# oresat1b-minusz-end-cap.net
KiCad netlist of a schematic drawn in EAGLE
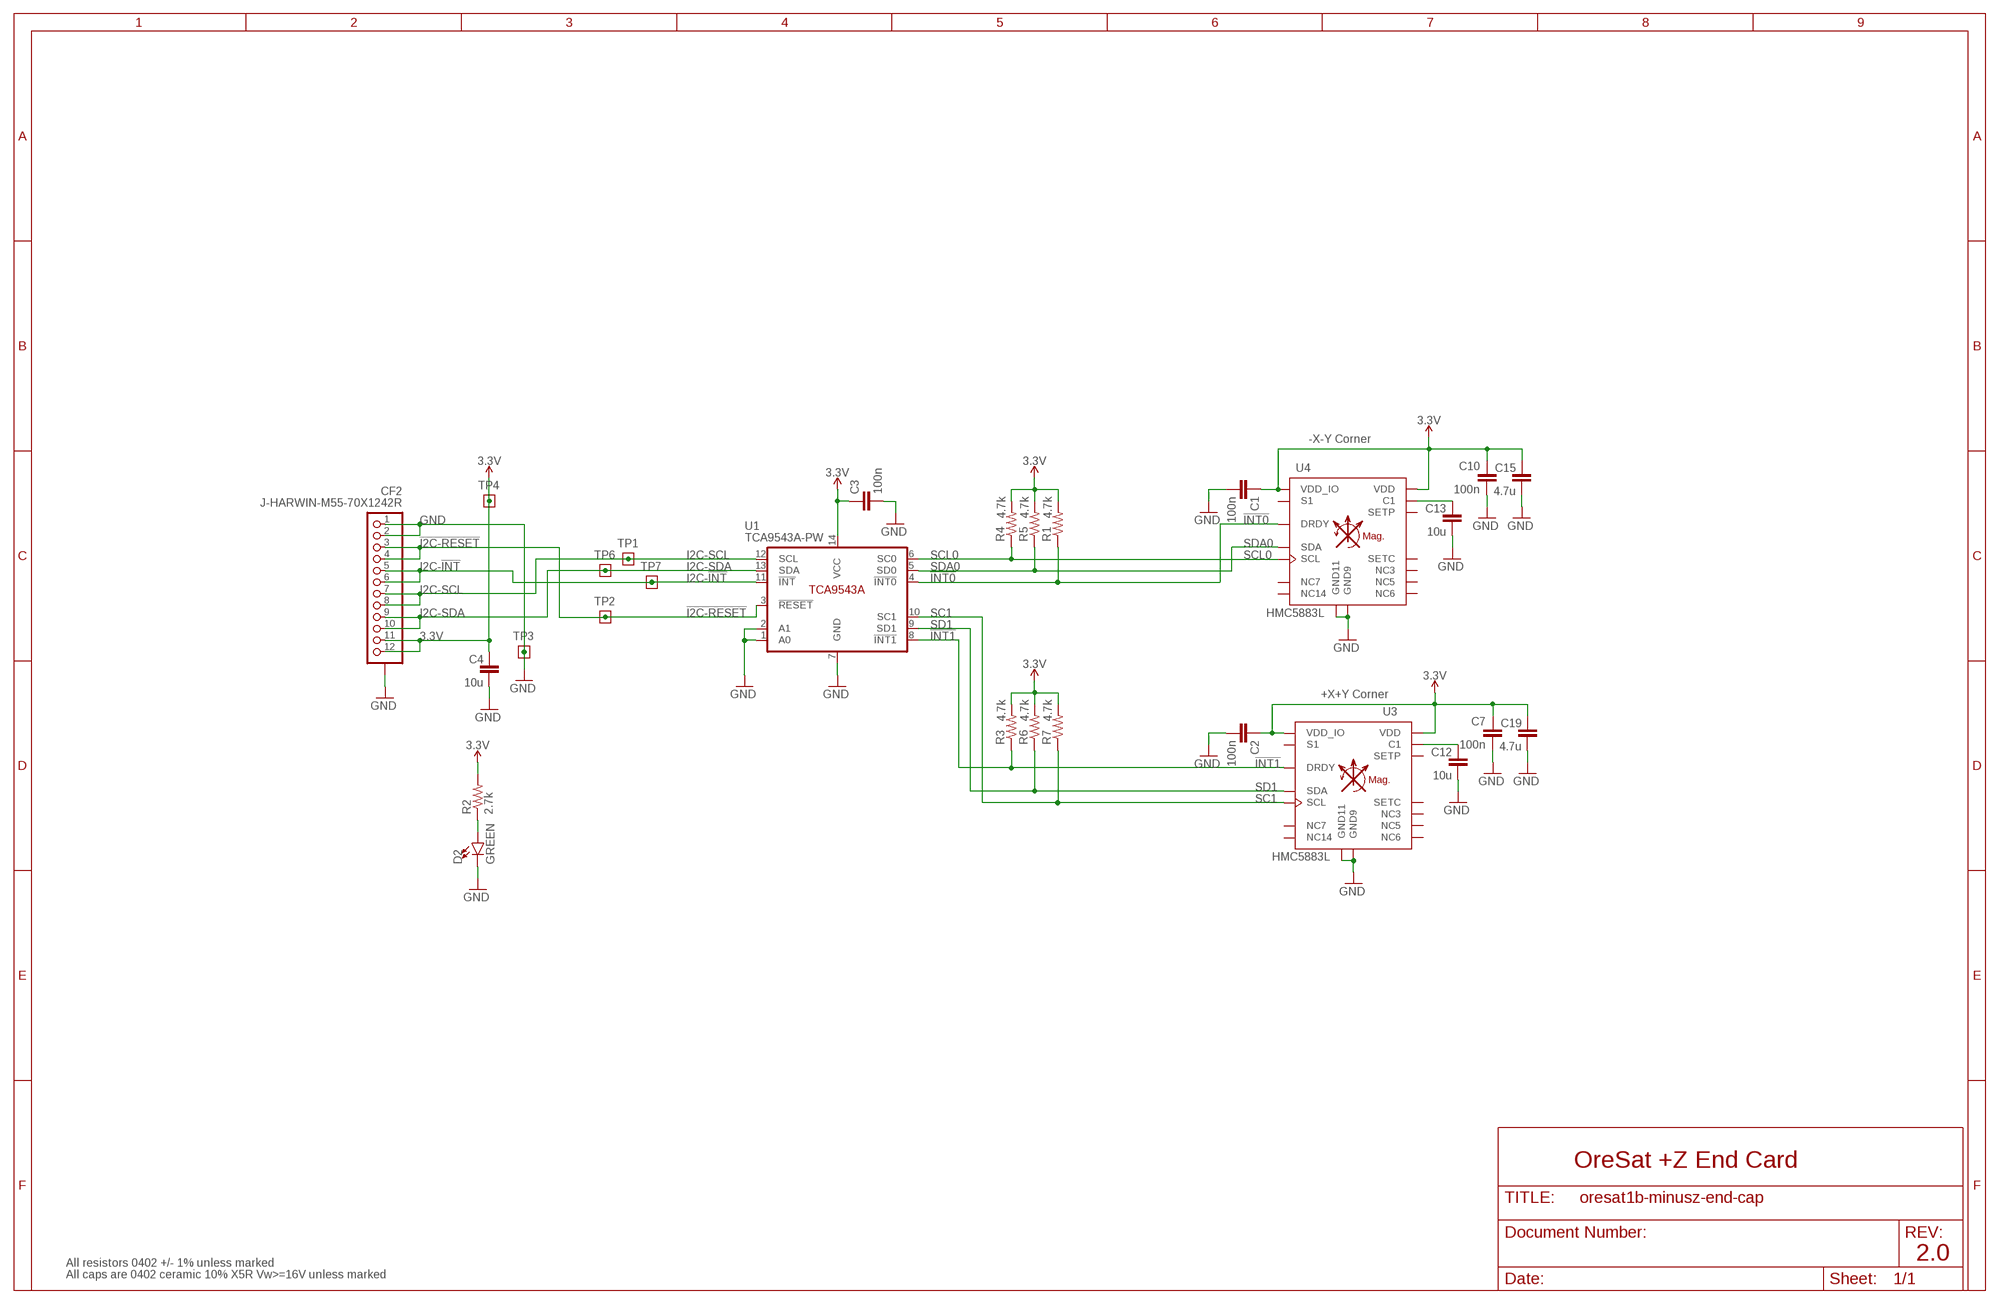
[diagram p0: schematic, sheet 1]

(export (version "E")
  (design (tool "Eeschema 10.0.6"))
  (components
    (comp (ref "C1")
      (value "100n")
      (footprint "eagle-import:.0402-B-NOSILK")
      (fields (field (name "MFR") "Samsung") (field (name "MPN") "CL05B104KO5NNNC"))
      (libsource (lib "eagle-import") (part "rcl_custom_C-EU0402-B-NOSILK"))
    )
    (comp (ref "C2")
      (value "100n")
      (footprint "eagle-import:.0402-B-NOSILK")
      (fields (field (name "MFR") "Samsung") (field (name "MPN") "CL05B104KO5NNNC"))
      (libsource (lib "eagle-import") (part "rcl_custom_C-EU0402-B-NOSILK"))
    )
    (comp (ref "C3")
      (value "100n")
      (footprint "eagle-import:.0402-B-NOSILK")
      (fields (field (name "MFR") "Samsung") (field (name "MPN") "CL05B104KO5NNNC"))
      (libsource (lib "eagle-import") (part "rcl_custom_C-EU0402-B-NOSILK"))
    )
    (comp (ref "C4")
      (value "10u")
      (footprint "eagle-import:.0603-B-NOSILK")
      (fields (field (name "MFR") "Samsung") (field (name "MPN") "CL05B104KO5NNNC"))
      (libsource (lib "eagle-import") (part "C-EU0603-B-NOSILK"))
    )
    (comp (ref "C7")
      (value "100n")
      (footprint "eagle-import:.0402-B-NOSILK")
      (fields (field (name "MFR") "Samsung") (field (name "MPN") "CL05B104KO5NNNC"))
      (libsource (lib "eagle-import") (part "rcl_custom_C-EU0402-B-NOSILK"))
    )
    (comp (ref "C10")
      (value "100n")
      (footprint "eagle-import:.0402-B-NOSILK")
      (fields (field (name "MFR") "Samsung") (field (name "MPN") "CL05B104KO5NNNC"))
      (libsource (lib "eagle-import") (part "rcl_custom_C-EU0402-B-NOSILK"))
    )
    (comp (ref "C12")
      (value "10u")
      (footprint "eagle-import:.0603-B-NOSILK")
      (fields (field (name "MFR") "Samsung") (field (name "MPN") "CL05B104KO5NNNC"))
      (libsource (lib "eagle-import") (part "C-EU0603-B-NOSILK"))
    )
    (comp (ref "C13")
      (value "10u")
      (footprint "eagle-import:.0603-B-NOSILK")
      (fields (field (name "MFR") "Samsung") (field (name "MPN") "CL05B104KO5NNNC"))
      (libsource (lib "eagle-import") (part "C-EU0603-B-NOSILK"))
    )
    (comp (ref "C15")
      (value "4.7u")
      (footprint "eagle-import:.0603-B-NOSILK")
      (fields (field (name "MFR") "Samsung") (field (name "MPN") "CL05B104KO5NNNC"))
      (libsource (lib "eagle-import") (part "C-EU0603-B-NOSILK"))
    )
    (comp (ref "C19")
      (value "4.7u")
      (footprint "eagle-import:.0603-B-NOSILK")
      (fields (field (name "MFR") "Samsung") (field (name "MPN") "CL05B104KO5NNNC"))
      (libsource (lib "eagle-import") (part "C-EU0603-B-NOSILK"))
    )
    (comp (ref "CF2")
      (value "J-HARWIN-M55-70X1242R")
      (footprint "eagle-import:HARWIN-M55-70X1242R")
      (libsource (lib "eagle-import") (part "J-HARWIN-M55-70X1242R"))
    )
    (comp (ref "D2")
      (value "GREEN")
      (footprint "eagle-import:LED-0603")
      (libsource (lib "eagle-import") (part "LED-GREEN0603"))
    )
    (comp (ref "R1")
      (value "4.7k")
      (footprint "eagle-import:.0402-B-NOSILK")
      (fields (field (name "MFR") "Samsung") (field (name "MPN") "RC1005F6653CS"))
      (libsource (lib "eagle-import") (part "R-US_0402-B-NOSILK"))
    )
    (comp (ref "R2")
      (value "2.7k")
      (footprint "eagle-import:.0402-B-NOSILK")
      (fields (field (name "MFR") "Samsung") (field (name "MPN") "RC1005F6653CS"))
      (libsource (lib "eagle-import") (part "R-US_0402-B-NOSILK"))
    )
    (comp (ref "R3")
      (value "4.7k")
      (footprint "eagle-import:.0402-B-NOSILK")
      (fields (field (name "MFR") "Samsung") (field (name "MPN") "RC1005F6653CS"))
      (libsource (lib "eagle-import") (part "R-US_0402-B-NOSILK"))
    )
    (comp (ref "R4")
      (value "4.7k")
      (footprint "eagle-import:.0402-B-NOSILK")
      (fields (field (name "MFR") "Samsung") (field (name "MPN") "RC1005F6653CS"))
      (libsource (lib "eagle-import") (part "R-US_0402-B-NOSILK"))
    )
    (comp (ref "R5")
      (value "4.7k")
      (footprint "eagle-import:.0402-B-NOSILK")
      (fields (field (name "MFR") "Samsung") (field (name "MPN") "RC1005F6653CS"))
      (libsource (lib "eagle-import") (part "R-US_0402-B-NOSILK"))
    )
    (comp (ref "R6")
      (value "4.7k")
      (footprint "eagle-import:.0402-B-NOSILK")
      (fields (field (name "MFR") "Samsung") (field (name "MPN") "RC1005F6653CS"))
      (libsource (lib "eagle-import") (part "R-US_0402-B-NOSILK"))
    )
    (comp (ref "R7")
      (value "4.7k")
      (footprint "eagle-import:.0402-B-NOSILK")
      (fields (field (name "MFR") "Samsung") (field (name "MPN") "RC1005F6653CS"))
      (libsource (lib "eagle-import") (part "R-US_0402-B-NOSILK"))
    )
    (comp (ref "TP1")
      (value "TEST-POINT")
      (footprint "eagle-import:2MM-TEST-POINT")
      (libsource (lib "eagle-import") (part "TEST-POINT"))
    )
    (comp (ref "TP2")
      (value "TEST-POINT")
      (footprint "eagle-import:2MM-TEST-POINT")
      (libsource (lib "eagle-import") (part "TEST-POINT"))
    )
    (comp (ref "TP3")
      (value "TEST-POINT")
      (footprint "eagle-import:2MM-TEST-POINT")
      (libsource (lib "eagle-import") (part "TEST-POINT"))
    )
    (comp (ref "TP4")
      (value "TEST-POINT")
      (footprint "eagle-import:2MM-TEST-POINT")
      (libsource (lib "eagle-import") (part "TEST-POINT"))
    )
    (comp (ref "TP6")
      (value "TEST-POINT")
      (footprint "eagle-import:2MM-TEST-POINT")
      (libsource (lib "eagle-import") (part "TEST-POINT"))
    )
    (comp (ref "TP7")
      (value "TEST-POINT")
      (footprint "eagle-import:2MM-TEST-POINT")
      (libsource (lib "eagle-import") (part "TEST-POINT"))
    )
    (comp (ref "U1")
      (value "TCA9543A-PW")
      (footprint "eagle-import:TSSOP14-0.65-5.4X4.4MM")
      (libsource (lib "eagle-import") (part "TCA9543A-PW"))
    )
    (comp (ref "U3")
      (value "HMC5883L")
      (footprint "eagle-import:QLGA-16(3X3)")
      (libsource (lib "eagle-import") (part "HMC5883L-LGA-16"))
    )
    (comp (ref "U4")
      (value "HMC5883L")
      (footprint "eagle-import:QLGA-16(3X3)")
      (libsource (lib "eagle-import") (part "HMC5883L-LGA-16"))
    )
  )
  (nets
    (net (code "1") (name "/I2C-SCL") (class "Default")
      (node (ref "CF2") (pin "7") (pinfunction "7_7") (pintype "passive"))
      (node (ref "CF2") (pin "8") (pinfunction "8_8") (pintype "passive"))
      (node (ref "TP1") (pin "1") (pinfunction "1_1") (pintype "passive"))
      (node (ref "U1") (pin "12") (pinfunction "SCL_12") (pintype "input"))
    )
    (net (code "2") (name "/I2C-SDA") (class "Default")
      (node (ref "CF2") (pin "10") (pinfunction "10_10") (pintype "passive"))
      (node (ref "CF2") (pin "9") (pinfunction "9_9") (pintype "passive"))
      (node (ref "TP6") (pin "1") (pinfunction "1_1") (pintype "passive"))
      (node (ref "U1") (pin "13") (pinfunction "SDA_13") (pintype "bidirectional"))
    )
    (net (code "3") (name "/I2C-~{INT}") (class "Default")
      (node (ref "CF2") (pin "5") (pinfunction "5_5") (pintype "passive"))
      (node (ref "CF2") (pin "6") (pinfunction "6_6") (pintype "passive"))
      (node (ref "TP7") (pin "1") (pinfunction "1_1") (pintype "passive"))
      (node (ref "U1") (pin "11") (pinfunction "~{INT}_11") (pintype "open_collector"))
    )
    (net (code "4") (name "/SC1") (class "Default")
      (node (ref "R7") (pin "1") (pinfunction "1_1") (pintype "passive"))
      (node (ref "U1") (pin "10") (pinfunction "SC1_10") (pintype "output"))
      (node (ref "U3") (pin "1") (pinfunction "SCL_1") (pintype "input"))
    )
    (net (code "5") (name "/SCL0") (class "Default")
      (node (ref "R4") (pin "1") (pinfunction "1_1") (pintype "passive"))
      (node (ref "U1") (pin "6") (pinfunction "SC0_6") (pintype "output"))
      (node (ref "U4") (pin "1") (pinfunction "SCL_1") (pintype "input"))
    )
    (net (code "6") (name "/SD1") (class "Default")
      (node (ref "R6") (pin "1") (pinfunction "1_1") (pintype "passive"))
      (node (ref "U1") (pin "9") (pinfunction "SD1_9") (pintype "bidirectional"))
      (node (ref "U3") (pin "16") (pinfunction "SDA_16") (pintype "bidirectional"))
    )
    (net (code "7") (name "/SDA0") (class "Default")
      (node (ref "R5") (pin "1") (pinfunction "1_1") (pintype "passive"))
      (node (ref "U1") (pin "5") (pinfunction "SD0_5") (pintype "bidirectional"))
      (node (ref "U4") (pin "16") (pinfunction "SDA_16") (pintype "bidirectional"))
    )
    (net (code "8") (name "/~{I2C-RESET}") (class "Default")
      (node (ref "CF2") (pin "3") (pinfunction "3_3") (pintype "passive"))
      (node (ref "CF2") (pin "4") (pinfunction "4_4") (pintype "passive"))
      (node (ref "TP2") (pin "1") (pinfunction "1_1") (pintype "passive"))
      (node (ref "U1") (pin "3") (pinfunction "~{RESET}_3") (pintype "input"))
    )
    (net (code "9") (name "/~{INT0}") (class "Default")
      (node (ref "R1") (pin "1") (pinfunction "1_1") (pintype "passive"))
      (node (ref "U1") (pin "4") (pinfunction "~{INT0}_4") (pintype "input"))
      (node (ref "U4") (pin "15") (pinfunction "DRDY_15") (pintype "output"))
    )
    (net (code "10") (name "/~{INT1}") (class "Default")
      (node (ref "R3") (pin "1") (pinfunction "1_1") (pintype "passive"))
      (node (ref "U1") (pin "8") (pinfunction "~{INT1}_8") (pintype "input"))
      (node (ref "U3") (pin "15") (pinfunction "DRDY_15") (pintype "output"))
    )
    (net (code "11") (name "3.3V") (class "Default")
      (node (ref "C1") (pin "1") (pinfunction "1_1") (pintype "passive"))
      (node (ref "C10") (pin "1") (pinfunction "1_1") (pintype "passive"))
      (node (ref "C15") (pin "1") (pinfunction "1_1") (pintype "passive"))
      (node (ref "C19") (pin "1") (pinfunction "1_1") (pintype "passive"))
      (node (ref "C2") (pin "1") (pinfunction "1_1") (pintype "passive"))
      (node (ref "C3") (pin "1") (pinfunction "1_1") (pintype "passive"))
      (node (ref "C4") (pin "1") (pinfunction "1_1") (pintype "passive"))
      (node (ref "C7") (pin "1") (pinfunction "1_1") (pintype "passive"))
      (node (ref "CF2") (pin "11") (pinfunction "11_11") (pintype "passive"))
      (node (ref "CF2") (pin "12") (pinfunction "12_12") (pintype "passive"))
      (node (ref "R1") (pin "2") (pinfunction "2_2") (pintype "passive"))
      (node (ref "R2") (pin "2") (pinfunction "2_2") (pintype "passive"))
      (node (ref "R3") (pin "2") (pinfunction "2_2") (pintype "passive"))
      (node (ref "R4") (pin "2") (pinfunction "2_2") (pintype "passive"))
      (node (ref "R5") (pin "2") (pinfunction "2_2") (pintype "passive"))
      (node (ref "R6") (pin "2") (pinfunction "2_2") (pintype "passive"))
      (node (ref "R7") (pin "2") (pinfunction "2_2") (pintype "passive"))
      (node (ref "TP4") (pin "1") (pinfunction "1_1") (pintype "passive"))
      (node (ref "U1") (pin "14") (pinfunction "VCC_14") (pintype "power_in"))
      (node (ref "U3") (pin "13") (pinfunction "VDD_IO_13") (pintype "power_in"))
      (node (ref "U3") (pin "2") (pinfunction "VDD_2") (pintype "power_in"))
      (node (ref "U4") (pin "13") (pinfunction "VDD_IO_13") (pintype "power_in"))
      (node (ref "U4") (pin "2") (pinfunction "VDD_2") (pintype "power_in"))
    )
    (net (code "12") (name "GND") (class "Default")
      (node (ref "C1") (pin "2") (pinfunction "2_2") (pintype "passive"))
      (node (ref "C10") (pin "2") (pinfunction "2_2") (pintype "passive"))
      (node (ref "C12") (pin "2") (pinfunction "2_2") (pintype "passive"))
      (node (ref "C13") (pin "2") (pinfunction "2_2") (pintype "passive"))
      (node (ref "C15") (pin "2") (pinfunction "2_2") (pintype "passive"))
      (node (ref "C19") (pin "2") (pinfunction "2_2") (pintype "passive"))
      (node (ref "C2") (pin "2") (pinfunction "2_2") (pintype "passive"))
      (node (ref "C3") (pin "2") (pinfunction "2_2") (pintype "passive"))
      (node (ref "C4") (pin "2") (pinfunction "2_2") (pintype "passive"))
      (node (ref "C7") (pin "2") (pinfunction "2_2") (pintype "passive"))
      (node (ref "CF2") (pin "1") (pinfunction "1_1") (pintype "passive"))
      (node (ref "CF2") (pin "2") (pinfunction "2_2") (pintype "passive"))
      (node (ref "CF2") (pin "P$1") (pinfunction "SHIELDS_P$1") (pintype "passive"))
      (node (ref "CF2") (pin "P$2") (pinfunction "SHIELDS_P$2") (pintype "passive"))
      (node (ref "CF2") (pin "P$3") (pinfunction "SHIELDS_P$3") (pintype "passive"))
      (node (ref "CF2") (pin "P$4") (pinfunction "SHIELDS_P$4") (pintype "passive"))
      (node (ref "D2") (pin "C") (pinfunction "C_C") (pintype "passive"))
      (node (ref "TP3") (pin "1") (pinfunction "1_1") (pintype "passive"))
      (node (ref "U1") (pin "1") (pinfunction "A0_1") (pintype "input"))
      (node (ref "U1") (pin "2") (pinfunction "A1_2") (pintype "input"))
      (node (ref "U1") (pin "7") (pinfunction "GND_7") (pintype "power_in"))
      (node (ref "U3") (pin "11") (pinfunction "GND11_11") (pintype "power_in"))
      (node (ref "U3") (pin "9") (pinfunction "GND9_9") (pintype "power_in"))
      (node (ref "U4") (pin "11") (pinfunction "GND11_11") (pintype "power_in"))
      (node (ref "U4") (pin "9") (pinfunction "GND9_9") (pintype "power_in"))
    )
    (net (code "13") (name "Net-(D2-PadA)") (class "Default")
      (node (ref "D2") (pin "A") (pinfunction "A_A") (pintype "passive"))
      (node (ref "R2") (pin "1") (pinfunction "1_1") (pintype "passive"))
    )
    (net (code "14") (name "Net-(U3-C1)") (class "Default")
      (node (ref "C12") (pin "1") (pinfunction "1_1") (pintype "passive"))
      (node (ref "U3") (pin "10") (pinfunction "C1_10") (pintype "passive"))
    )
    (net (code "15") (name "Net-(U4-C1)") (class "Default")
      (node (ref "C13") (pin "1") (pinfunction "1_1") (pintype "passive"))
      (node (ref "U4") (pin "10") (pinfunction "C1_10") (pintype "passive"))
    )
    (net (code "16") (name "unconnected-(U3-NC3-Pad3)") (class "Default")
      (node (ref "U3") (pin "3") (pinfunction "NC3_3") (pintype "no_connect"))
    )
    (net (code "17") (name "unconnected-(U3-NC5-Pad5)") (class "Default")
      (node (ref "U3") (pin "5") (pinfunction "NC5_5") (pintype "no_connect"))
    )
    (net (code "18") (name "unconnected-(U3-NC6-Pad6)") (class "Default")
      (node (ref "U3") (pin "6") (pinfunction "NC6_6") (pintype "no_connect"))
    )
    (net (code "19") (name "unconnected-(U3-NC7-Pad7)") (class "Default")
      (node (ref "U3") (pin "7") (pinfunction "NC7_7") (pintype "no_connect"))
    )
    (net (code "20") (name "unconnected-(U3-NC14-Pad14)") (class "Default")
      (node (ref "U3") (pin "14") (pinfunction "NC14_14") (pintype "no_connect"))
    )
    (net (code "21") (name "unconnected-(U3-S1-Pad4)") (class "Default")
      (node (ref "U3") (pin "4") (pinfunction "S1_4") (pintype "input"))
    )
    (net (code "22") (name "unconnected-(U3-SETC-Pad12)") (class "Default")
      (node (ref "U3") (pin "12") (pinfunction "SETC_12") (pintype "output"))
    )
    (net (code "23") (name "unconnected-(U3-SETP-Pad8)") (class "Default")
      (node (ref "U3") (pin "8") (pinfunction "SETP_8") (pintype "passive"))
    )
    (net (code "24") (name "unconnected-(U4-NC3-Pad3)") (class "Default")
      (node (ref "U4") (pin "3") (pinfunction "NC3_3") (pintype "no_connect"))
    )
    (net (code "25") (name "unconnected-(U4-NC5-Pad5)") (class "Default")
      (node (ref "U4") (pin "5") (pinfunction "NC5_5") (pintype "no_connect"))
    )
    (net (code "26") (name "unconnected-(U4-NC6-Pad6)") (class "Default")
      (node (ref "U4") (pin "6") (pinfunction "NC6_6") (pintype "no_connect"))
    )
    (net (code "27") (name "unconnected-(U4-NC7-Pad7)") (class "Default")
      (node (ref "U4") (pin "7") (pinfunction "NC7_7") (pintype "no_connect"))
    )
    (net (code "28") (name "unconnected-(U4-NC14-Pad14)") (class "Default")
      (node (ref "U4") (pin "14") (pinfunction "NC14_14") (pintype "no_connect"))
    )
    (net (code "29") (name "unconnected-(U4-S1-Pad4)") (class "Default")
      (node (ref "U4") (pin "4") (pinfunction "S1_4") (pintype "input"))
    )
    (net (code "30") (name "unconnected-(U4-SETC-Pad12)") (class "Default")
      (node (ref "U4") (pin "12") (pinfunction "SETC_12") (pintype "output"))
    )
    (net (code "31") (name "unconnected-(U4-SETP-Pad8)") (class "Default")
      (node (ref "U4") (pin "8") (pinfunction "SETP_8") (pintype "passive"))
    )
  )
)
